# BLDC1.net
KiCad netlist of a schematic drawn in Altium Designer
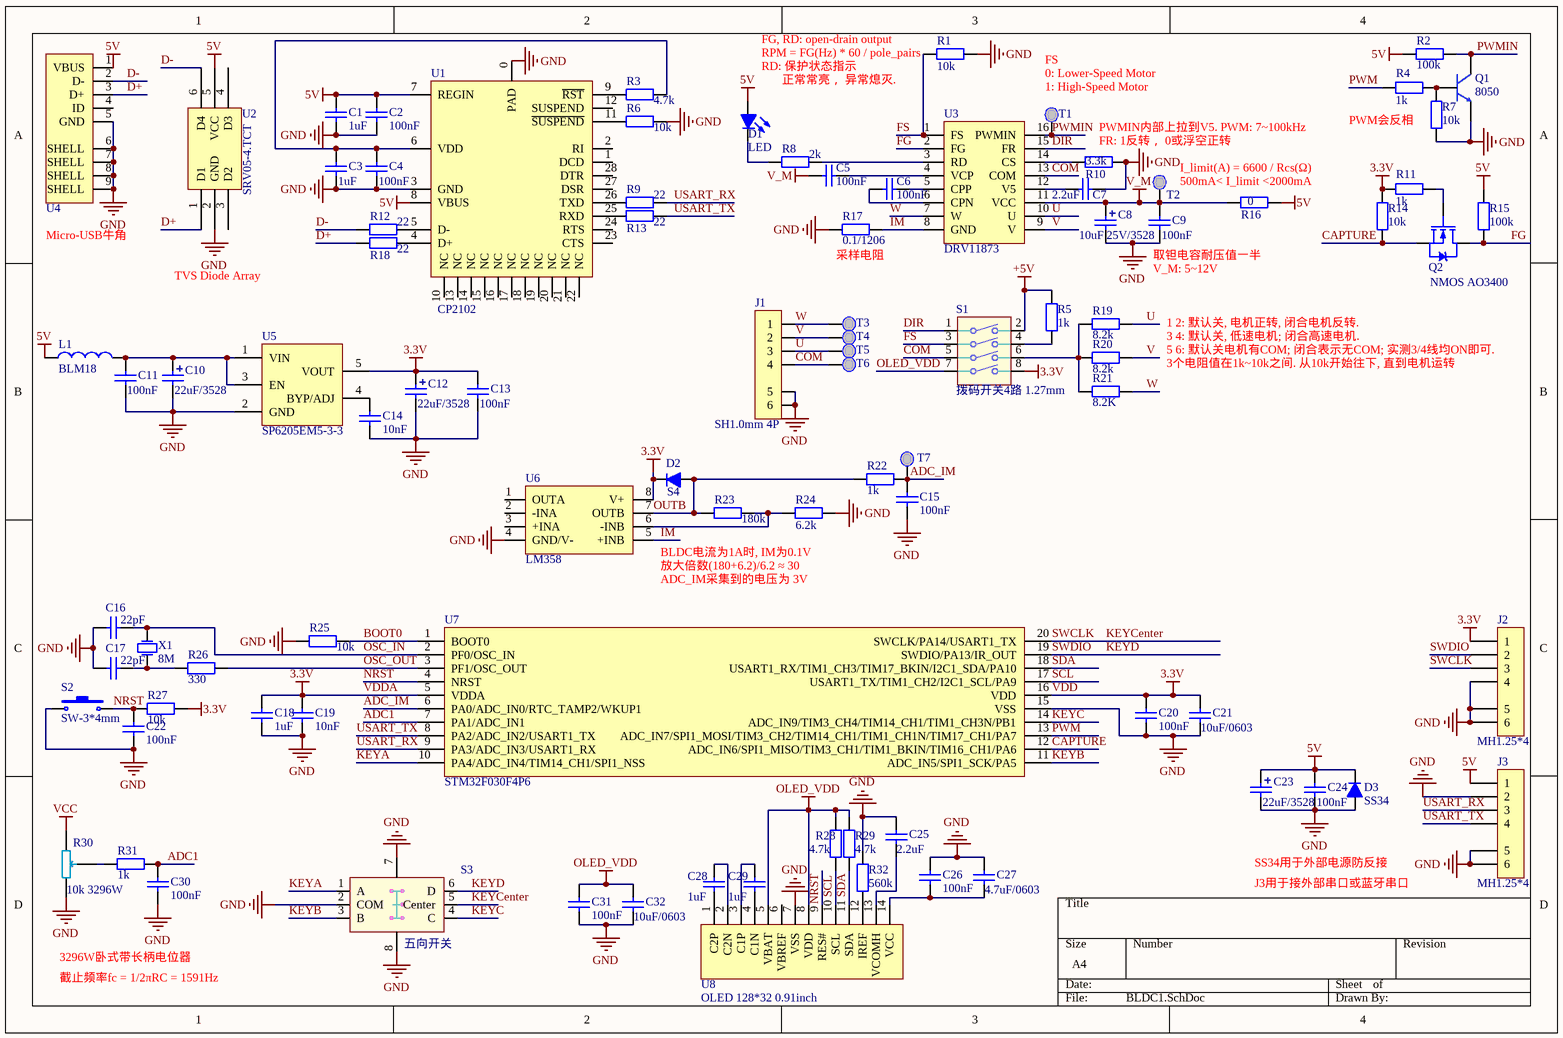
[diagram p0: BLDC1.SchDoc]

(export (version "E")
  (design (tool "Eeschema 10.0.6"))
  (components
    (comp (ref "C1")
      (value "1uF")
      (footprint "C0402")
      (description "Capacitor")
      (fields (field (name "Comment") "Cap1") (field (name "PUBLISHER") "Altium Limited"))
      (libsource (lib "weifengdq") (part "Cap1"))
    )
    (comp (ref "C2")
      (value "100nF")
      (footprint "C0402")
      (description "Capacitor")
      (fields (field (name "Comment") "Cap1") (field (name "PUBLISHER") "Altium Limited"))
      (libsource (lib "weifengdq") (part "Cap1"))
    )
    (comp (ref "C3")
      (value "1uF")
      (footprint "C0402")
      (description "Capacitor")
      (fields (field (name "Comment") "Cap1") (field (name "PUBLISHER") "Altium Limited"))
      (libsource (lib "weifengdq") (part "Cap1"))
    )
    (comp (ref "C4")
      (value "100nF")
      (footprint "C0402")
      (description "Capacitor")
      (fields (field (name "Comment") "Cap1") (field (name "PUBLISHER") "Altium Limited"))
      (libsource (lib "weifengdq") (part "Cap1"))
    )
    (comp (ref "C5")
      (value "100nF")
      (footprint "C0402")
      (description "Capacitor")
      (fields (field (name "Comment") "Cap1") (field (name "PUBLISHER") "Altium Limited"))
      (libsource (lib "weifengdq") (part "Cap1"))
    )
    (comp (ref "C6")
      (value "100nF")
      (footprint "C0402")
      (description "Capacitor")
      (fields (field (name "Comment") "Cap1") (field (name "PUBLISHER") "Altium Limited"))
      (libsource (lib "weifengdq") (part "Cap1"))
    )
    (comp (ref "C7")
      (value "2.2uF")
      (footprint "0603")
      (description "Capacitor")
      (fields (field (name "Comment") "Cap1") (field (name "PUBLISHER") "Altium Limited"))
      (libsource (lib "weifengdq") (part "Cap1"))
    )
    (comp (ref "C8")
      (value "10uF 25V/3528")
      (footprint "3528(22u16V钽电容)")
      (description "Capacitor")
      (fields (field (name "Comment") "Cap_Pol") (field (name "PUBLISHER") "Altium Limited"))
      (libsource (lib "weifengdq") (part "Cap_Pol"))
    )
    (comp (ref "C9")
      (value "100nF")
      (footprint "C0402")
      (description "Capacitor")
      (fields (field (name "Comment") "Cap1") (field (name "PUBLISHER") "Altium Limited"))
      (libsource (lib "weifengdq") (part "Cap1"))
    )
    (comp (ref "C10")
      (value "22uF/3528")
      (footprint "3528(22u16V钽电容)")
      (description "Capacitor")
      (fields (field (name "Comment") "Cap_Pol") (field (name "PUBLISHER") "Altium Limited"))
      (libsource (lib "weifengdq") (part "Cap_Pol"))
    )
    (comp (ref "C11")
      (value "100nF")
      (footprint "C0402")
      (description "Capacitor")
      (fields (field (name "Comment") "Cap1") (field (name "PUBLISHER") "Altium Limited"))
      (libsource (lib "weifengdq") (part "Cap1"))
    )
    (comp (ref "C12")
      (value "22uF/3528")
      (footprint "3528(22u16V钽电容)")
      (description "Capacitor")
      (fields (field (name "Comment") "Cap_Pol") (field (name "PUBLISHER") "Altium Limited"))
      (libsource (lib "weifengdq") (part "Cap_Pol"))
    )
    (comp (ref "C13")
      (value "100nF")
      (footprint "C0402")
      (description "Capacitor")
      (fields (field (name "Comment") "Cap1") (field (name "PUBLISHER") "Altium Limited"))
      (libsource (lib "weifengdq") (part "Cap1"))
    )
    (comp (ref "C14")
      (value "10nF")
      (footprint "C0402")
      (description "Capacitor")
      (fields (field (name "Comment") "Cap1") (field (name "PUBLISHER") "Altium Limited"))
      (libsource (lib "weifengdq") (part "Cap1"))
    )
    (comp (ref "C15")
      (value "100nF")
      (footprint "C0402")
      (description "Capacitor")
      (fields (field (name "Comment") "Cap1") (field (name "PUBLISHER") "Altium Limited"))
      (libsource (lib "weifengdq") (part "Cap1"))
    )
    (comp (ref "C16")
      (value "22pF")
      (footprint "C0402")
      (description "Capacitor")
      (fields (field (name "Comment") "Cap1") (field (name "PUBLISHER") "Altium Limited"))
      (libsource (lib "weifengdq") (part "Cap1"))
    )
    (comp (ref "C17")
      (value "22pF")
      (footprint "C0402")
      (description "Capacitor")
      (fields (field (name "Comment") "Cap1") (field (name "PUBLISHER") "Altium Limited"))
      (libsource (lib "weifengdq") (part "Cap1"))
    )
    (comp (ref "C18")
      (value "1uF")
      (footprint "C0402")
      (description "Capacitor")
      (fields (field (name "Comment") "Cap1") (field (name "PUBLISHER") "Altium Limited"))
      (libsource (lib "weifengdq") (part "Cap1"))
    )
    (comp (ref "C19")
      (value "10nF")
      (footprint "C0402")
      (description "Capacitor")
      (fields (field (name "Comment") "Cap1") (field (name "PUBLISHER") "Altium Limited"))
      (libsource (lib "weifengdq") (part "Cap1"))
    )
    (comp (ref "C20")
      (value "100nF")
      (footprint "C0402")
      (description "Capacitor")
      (fields (field (name "Comment") "Cap1") (field (name "PUBLISHER") "Altium Limited"))
      (libsource (lib "weifengdq") (part "Cap1"))
    )
    (comp (ref "C21")
      (value "10uF/0603")
      (footprint "0603")
      (description "Capacitor")
      (fields (field (name "Comment") "Cap1") (field (name "PUBLISHER") "Altium Limited"))
      (libsource (lib "weifengdq") (part "Cap1"))
    )
    (comp (ref "C22")
      (value "100nF")
      (footprint "C0402")
      (description "Capacitor")
      (fields (field (name "Comment") "Cap1") (field (name "PUBLISHER") "Altium Limited"))
      (libsource (lib "weifengdq") (part "Cap1"))
    )
    (comp (ref "C23")
      (value "22uF/3528")
      (footprint "3528(22u16V钽电容)")
      (description "Capacitor")
      (fields (field (name "Comment") "Cap_Pol") (field (name "PUBLISHER") "Altium Limited"))
      (libsource (lib "weifengdq") (part "Cap_Pol"))
    )
    (comp (ref "C24")
      (value "100nF")
      (footprint "C0402")
      (description "Capacitor")
      (fields (field (name "Comment") "Cap1") (field (name "PUBLISHER") "Altium Limited"))
      (libsource (lib "weifengdq") (part "Cap1"))
    )
    (comp (ref "C25")
      (value "2.2uF")
      (footprint "0603")
      (description "Capacitor")
      (fields (field (name "Comment") "Cap1") (field (name "PUBLISHER") "Altium Limited"))
      (libsource (lib "weifengdq") (part "Cap1"))
    )
    (comp (ref "C26")
      (value "100nF")
      (footprint "C0402")
      (description "Capacitor")
      (fields (field (name "Comment") "Cap1") (field (name "PUBLISHER") "Altium Limited"))
      (libsource (lib "weifengdq") (part "Cap1"))
    )
    (comp (ref "C27")
      (value "4.7uF/0603")
      (footprint "0603")
      (description "Capacitor")
      (fields (field (name "Comment") "Cap1") (field (name "PUBLISHER") "Altium Limited"))
      (libsource (lib "weifengdq") (part "Cap1"))
    )
    (comp (ref "C28")
      (value "1uF")
      (footprint "C0402")
      (description "Capacitor")
      (fields (field (name "Comment") "Cap1") (field (name "PUBLISHER") "Altium Limited"))
      (libsource (lib "weifengdq") (part "Cap1"))
    )
    (comp (ref "C29")
      (value "1uF")
      (footprint "C0402")
      (description "Capacitor")
      (fields (field (name "Comment") "Cap1") (field (name "PUBLISHER") "Altium Limited"))
      (libsource (lib "weifengdq") (part "Cap1"))
    )
    (comp (ref "C30")
      (value "100nF")
      (footprint "C0402")
      (description "Capacitor")
      (fields (field (name "Comment") "Cap1") (field (name "PUBLISHER") "Altium Limited"))
      (libsource (lib "weifengdq") (part "Cap1"))
    )
    (comp (ref "C31")
      (value "100nF")
      (footprint "C0402")
      (description "Capacitor")
      (fields (field (name "Comment") "Cap1") (field (name "PUBLISHER") "Altium Limited"))
      (libsource (lib "weifengdq") (part "Cap1"))
    )
    (comp (ref "C32")
      (value "10uF/0603")
      (footprint "0603")
      (description "Capacitor")
      (fields (field (name "Comment") "Cap1") (field (name "PUBLISHER") "Altium Limited"))
      (libsource (lib "weifengdq") (part "Cap1"))
    )
    (comp (ref "D1")
      (value "LED")
      (footprint "DIODE-12")
      (description "Typical INFRARED GaAs LED")
      (fields (field (name "PUBLISHER") "Altium Limited"))
      (libsource (lib "weifengdq") (part "LED1"))
    )
    (comp (ref "D2") (value "S4") (footprint "Diode-0805") (libsource (lib "weifengdq") (part "Diode1")))
    (comp (ref "D3")
      (value "SS34")
      (footprint "LC-SMA(DO-214AC)_S2")
      (libsource (lib "weifengdq") (part "Diode1"))
    )
    (comp (ref "J1")
      (value "SH1.0mm 4P")
      (footprint "SH1.0 4P")
      (libsource (lib "weifengdq") (part "SH1.0mm 4P"))
    )
    (comp (ref "J2")
      (value "MH1.25*4")
      (footprint "MH1.25*4立式表贴")
      (libsource (lib "weifengdq") (part "MH1.25*4卧式贴片"))
    )
    (comp (ref "J3")
      (value "MH1.25*4")
      (footprint "MH1.25*4立式表贴")
      (libsource (lib "weifengdq") (part "MH1.25*4卧式贴片"))
    )
    (comp (ref "L1") (value "BLM18") (footprint "CC0805") (libsource (lib "weifengdq") (part "BLM18")))
    (comp (ref "Q1") (value "8050") (footprint "SOT-23-3") (libsource (lib "weifengdq") (part "NPN")))
    (comp (ref "Q2")
      (value "NMOS AO3400")
      (footprint "SOT-23-3 - AO3400")
      (description "N-Channel Power MOSFET")
      (fields (field (name "PUBLISHER") "Altium Limited"))
      (libsource (lib "weifengdq") (part "NMOS"))
    )
    (comp (ref "R1")
      (value "10k")
      (footprint "C0402")
      (description "Resistor")
      (fields (field (name "Comment") "Res1") (field (name "PUBLISHER") "Altium Limited"))
      (libsource (lib "") (part "Res1_1"))
    )
    (comp (ref "R2")
      (value "100k")
      (footprint "C0402")
      (description "Resistor")
      (fields (field (name "Comment") "Res1") (field (name "PUBLISHER") "Altium Limited"))
      (libsource (lib "") (part "Res1_1"))
    )
    (comp (ref "R3")
      (value "4.7k")
      (footprint "C0402")
      (description "Resistor")
      (fields (field (name "Comment") "Res1") (field (name "PUBLISHER") "Altium Limited"))
      (libsource (lib "weifengdq") (part "Res1"))
    )
    (comp (ref "R4")
      (value "1k")
      (footprint "C0402")
      (description "Resistor")
      (fields (field (name "Comment") "Res1") (field (name "PUBLISHER") "Altium Limited"))
      (libsource (lib "weifengdq") (part "Res1"))
    )
    (comp (ref "R5")
      (value "1k")
      (footprint "C0402")
      (description "Resistor")
      (fields (field (name "Comment") "Res1") (field (name "PUBLISHER") "Altium Limited"))
      (libsource (lib "") (part "Res1_3"))
    )
    (comp (ref "R6")
      (value "10k")
      (footprint "C0402")
      (description "Resistor")
      (fields (field (name "Comment") "Res1") (field (name "PUBLISHER") "Altium Limited"))
      (libsource (lib "weifengdq") (part "Res1"))
    )
    (comp (ref "R7")
      (value "10k")
      (footprint "C0402")
      (description "Resistor")
      (fields (field (name "Comment") "Res1") (field (name "PUBLISHER") "Altium Limited"))
      (libsource (lib "") (part "Res1_2"))
    )
    (comp (ref "R8")
      (value "2k")
      (footprint "C0402")
      (description "Resistor")
      (fields (field (name "Comment") "Res1") (field (name "PUBLISHER") "Altium Limited"))
      (libsource (lib "") (part "Res1_1"))
    )
    (comp (ref "R9")
      (value "22")
      (footprint "C0402")
      (description "Resistor")
      (fields (field (name "Comment") "Res1") (field (name "PUBLISHER") "Altium Limited"))
      (libsource (lib "weifengdq") (part "Res1"))
    )
    (comp (ref "R10")
      (value "3.3k")
      (footprint "C0402")
      (description "Resistor")
      (fields (field (name "Comment") "Res1") (field (name "PUBLISHER") "Altium Limited"))
      (libsource (lib "weifengdq") (part "Res1"))
    )
    (comp (ref "R11")
      (value "1k")
      (footprint "C0402")
      (description "Resistor")
      (fields (field (name "Comment") "Res1") (field (name "PUBLISHER") "Altium Limited"))
      (libsource (lib "weifengdq") (part "Res1"))
    )
    (comp (ref "R12")
      (value "22")
      (footprint "C0402")
      (description "Resistor")
      (fields (field (name "Comment") "Res1") (field (name "PUBLISHER") "Altium Limited"))
      (libsource (lib "weifengdq") (part "Res1"))
    )
    (comp (ref "R13")
      (value "22")
      (footprint "C0402")
      (description "Resistor")
      (fields (field (name "Comment") "Res1") (field (name "PUBLISHER") "Altium Limited"))
      (libsource (lib "weifengdq") (part "Res1"))
    )
    (comp (ref "R14")
      (value "10k")
      (footprint "C0402")
      (description "Resistor")
      (fields (field (name "Comment") "Res1") (field (name "PUBLISHER") "Altium Limited"))
      (libsource (lib "") (part "Res1_2"))
    )
    (comp (ref "R15")
      (value "100k")
      (footprint "C0402")
      (description "Resistor")
      (fields (field (name "Comment") "Res1") (field (name "PUBLISHER") "Altium Limited"))
      (libsource (lib "") (part "Res1_2"))
    )
    (comp (ref "R16")
      (value "0")
      (footprint "C0805")
      (description "Resistor")
      (fields (field (name "Comment") "Res1") (field (name "PUBLISHER") "Altium Limited"))
      (libsource (lib "weifengdq") (part "Res1"))
    )
    (comp (ref "R17")
      (value "0.1/1206")
      (footprint "3216[1206]")
      (description "Resistor")
      (fields (field (name "Comment") "Res1") (field (name "PUBLISHER") "Altium Limited"))
      (libsource (lib "") (part "Res1_1"))
    )
    (comp (ref "R18")
      (value "22")
      (footprint "C0402")
      (description "Resistor")
      (fields (field (name "Comment") "Res1") (field (name "PUBLISHER") "Altium Limited"))
      (libsource (lib "weifengdq") (part "Res1"))
    )
    (comp (ref "R19")
      (value "8.2k")
      (footprint "C0402")
      (description "Resistor")
      (fields (field (name "Comment") "Res1") (field (name "PUBLISHER") "Altium Limited"))
      (libsource (lib "") (part "Res1_1"))
    )
    (comp (ref "R20")
      (value "8.2k")
      (footprint "C0402")
      (description "Resistor")
      (fields (field (name "Comment") "Res1") (field (name "PUBLISHER") "Altium Limited"))
      (libsource (lib "") (part "Res1_1"))
    )
    (comp (ref "R21")
      (value "8.2K")
      (footprint "C0402")
      (description "Resistor")
      (fields (field (name "Comment") "Res1") (field (name "PUBLISHER") "Altium Limited"))
      (libsource (lib "") (part "Res1_1"))
    )
    (comp (ref "R22")
      (value "1k")
      (footprint "C0402")
      (description "Resistor")
      (fields (field (name "Comment") "Res1") (field (name "PUBLISHER") "Altium Limited"))
      (libsource (lib "") (part "Res1_1"))
    )
    (comp (ref "R23")
      (value "180k")
      (footprint "C0402")
      (description "Resistor")
      (fields (field (name "Comment") "Res1") (field (name "PUBLISHER") "Altium Limited"))
      (libsource (lib "weifengdq") (part "Res1"))
    )
    (comp (ref "R24")
      (value "6.2k")
      (footprint "C0402")
      (description "Resistor")
      (fields (field (name "Comment") "Res1") (field (name "PUBLISHER") "Altium Limited"))
      (libsource (lib "weifengdq") (part "Res1"))
    )
    (comp (ref "R25")
      (value "10k")
      (footprint "C0402")
      (description "Resistor")
      (fields (field (name "Comment") "Res1") (field (name "PUBLISHER") "Altium Limited"))
      (libsource (lib "") (part "Res1_1"))
    )
    (comp (ref "R26")
      (value "330")
      (footprint "C0402")
      (description "Resistor")
      (fields (field (name "Comment") "Res1") (field (name "PUBLISHER") "Altium Limited"))
      (libsource (lib "") (part "Res1_1"))
    )
    (comp (ref "R27")
      (value "10k")
      (footprint "C0402")
      (description "Resistor")
      (fields (field (name "Comment") "Res1") (field (name "PUBLISHER") "Altium Limited"))
      (libsource (lib "") (part "Res1_1"))
    )
    (comp (ref "R28")
      (value "4.7k")
      (footprint "C0402")
      (description "Resistor")
      (fields (field (name "Comment") "Res1") (field (name "PUBLISHER") "Altium Limited"))
      (libsource (lib "") (part "Res1_2"))
    )
    (comp (ref "R29")
      (value "4.7k")
      (footprint "C0402")
      (description "Resistor")
      (fields (field (name "Comment") "Res1") (field (name "PUBLISHER") "Altium Limited"))
      (libsource (lib "") (part "Res1_2"))
    )
    (comp (ref "R30")
      (value "10k 3296W")
      (footprint "3296W 卧式")
      (libsource (lib "weifengdq") (part "Res_3296"))
    )
    (comp (ref "R31")
      (value "1k")
      (footprint "C0402")
      (description "Resistor")
      (fields (field (name "Comment") "Res1") (field (name "PUBLISHER") "Altium Limited"))
      (libsource (lib "") (part "Res1_1"))
    )
    (comp (ref "R32")
      (value "560k")
      (footprint "C0402")
      (description "Resistor")
      (fields (field (name "Comment") "Res1") (field (name "PUBLISHER") "Altium Limited"))
      (libsource (lib "") (part "Res1_2"))
    )
    (comp (ref "S1")
      (value "拨码开关4路 1.27mm")
      (footprint "拨码开关4路")
      (libsource (lib "weifengdq") (part "拨码开关4路 1.27mm"))
    )
    (comp (ref "S2")
      (value "SW-3*4mm")
      (footprint "SW-3*4mm")
      (description "Switch")
      (fields (field (name "PUBLISHER") "Altium Limited"))
      (libsource (lib "weifengdq") (part "SW-3*4mm"))
    )
    (comp (ref "S3")
      (value "五向开关")
      (footprint "五向开关")
      (description "Switch")
      (fields (field (name "PUBLISHER") "Altium Limited"))
      (libsource (lib "weifengdq") (part "五向开关"))
    )
    (comp (ref "T1") (value "TEST") (footprint "TEST") (libsource (lib "weifengdq") (part "TEST")))
    (comp (ref "T2") (value "TEST") (footprint "TEST") (libsource (lib "weifengdq") (part "TEST")))
    (comp (ref "T3") (value "TEST") (footprint "TEST") (libsource (lib "weifengdq") (part "TEST")))
    (comp (ref "T4") (value "TEST") (footprint "TEST") (libsource (lib "weifengdq") (part "TEST")))
    (comp (ref "T5") (value "TEST") (footprint "TEST") (libsource (lib "weifengdq") (part "TEST")))
    (comp (ref "T6") (value "TEST") (footprint "TEST") (libsource (lib "weifengdq") (part "TEST")))
    (comp (ref "T7") (value "TEST") (footprint "TEST") (libsource (lib "weifengdq") (part "TEST")))
    (comp (ref "U1")
      (value "CP2102")
      (footprint "LC-QFN-28_5x5x05P")
      (libsource (lib "weifengdq") (part "CP2102"))
    )
    (comp (ref "U2")
      (value "SRV05-4.TCT")
      (footprint "LC-SOT-23-6")
      (libsource (lib "weifengdq") (part "SRV05-4.TCT"))
    )
    (comp (ref "U3")
      (value "DRV11873")
      (footprint "HTSSOP16")
      (libsource (lib "weifengdq") (part "DRV11873"))
    )
    (comp (ref "U4")
      (value "Micro-USB-N")
      (footprint "Micro-USB-N")
      (libsource (lib "weifengdq") (part "Micro-USB-N"))
    )
    (comp (ref "U5")
      (value "SP6205EM5-3-3")
      (footprint "LC-SOT-23-5")
      (libsource (lib "weifengdq") (part "SP6205EM5-L-3-3"))
    )
    (comp (ref "U6") (value "LM358") (footprint "LC-SOIC-8") (libsource (lib "weifengdq") (part "LM358")))
    (comp (ref "U7")
      (value "STM32F030F4P6")
      (footprint "TSSOP20")
      (libsource (lib "weifengdq") (part "STM32F030F4P6"))
    )
    (comp (ref "U8")
      (value "OLED 128*32 0.91inch")
      (footprint "OLED 0.91 I2C")
      (libsource (lib "weifengdq") (part "OLED 12832 I2C"))
    )
    (comp (ref "X1")
      (value "8M")
      (footprint "XTAL-3225")
      (description "Crystal Oscillator")
      (fields (field (name "PUBLISHER") "Altium Limited"))
      (libsource (lib "weifengdq") (part "XTAL_1"))
    )
  )
  (nets
    (net (code "1") (name "+5V") (class "Default")
      (node (ref "R5") (pin "1") (pinfunction "1_1") (pintype "passive"))
      (node (ref "S1") (pin "2") (pinfunction "2_2") (pintype "passive"))
    )
    (net (code "2") (name "/ADC1") (class "Default")
      (node (ref "C30") (pin "2") (pinfunction "2_2") (pintype "passive"))
      (node (ref "R31") (pin "1") (pinfunction "1_1") (pintype "passive"))
      (node (ref "U7") (pin "7") (pinfunction "PA1/ADC_IN1_7") (pintype "passive"))
    )
    (net (code "3") (name "/ADC_IM") (class "Default")
      (node (ref "C15") (pin "2") (pinfunction "2_2") (pintype "passive"))
      (node (ref "R22") (pin "1") (pinfunction "1_1") (pintype "passive"))
      (node (ref "T7") (pin "1") (pinfunction "1_1") (pintype "passive"))
      (node (ref "U7") (pin "6") (pinfunction "PA0/ADC_IN0/RTC_TAMP2/WKUP1_6") (pintype "passive"))
    )
    (net (code "4") (name "/BOOT0") (class "Default")
      (node (ref "R25") (pin "1") (pinfunction "1_1") (pintype "passive"))
      (node (ref "U7") (pin "1") (pinfunction "BOOT0_1") (pintype "passive"))
    )
    (net (code "5") (name "/CAPTURE") (class "Default")
      (node (ref "Q2") (pin "3") (pinfunction "S_3") (pintype "passive"))
      (node (ref "R14") (pin "1") (pinfunction "1_1") (pintype "passive"))
      (node (ref "U7") (pin "12") (pinfunction "ADC_IN6/SPI1_MISO/TIM3_CH1/TIM1_BKIN/TIM16_CH1/PA6_12") (pintype "passive"))
    )
    (net (code "6") (name "/COM") (class "Default")
      (node (ref "J1") (pin "4") (pinfunction "4_4") (pintype "passive"))
      (node (ref "S1") (pin "5") (pinfunction "5_5") (pintype "passive"))
      (node (ref "T6") (pin "1") (pinfunction "1_1") (pintype "passive"))
      (node (ref "U3") (pin "13") (pinfunction "COM_13") (pintype "passive"))
    )
    (net (code "7") (name "/D+") (class "Default")
      (node (ref "R18") (pin "1") (pinfunction "1_1") (pintype "passive"))
      (node (ref "U2") (pin "1") (pinfunction "D1_1") (pintype "passive"))
      (node (ref "U4") (pin "3") (pinfunction "D+_3") (pintype "passive"))
    )
    (net (code "8") (name "/D-") (class "Default")
      (node (ref "R12") (pin "1") (pinfunction "1_1") (pintype "passive"))
      (node (ref "U2") (pin "6") (pinfunction "D4_6") (pintype "passive"))
      (node (ref "U4") (pin "2") (pinfunction "D-_2") (pintype "passive"))
    )
    (net (code "9") (name "/DIR") (class "Default")
      (node (ref "S1") (pin "1") (pinfunction "1_1") (pintype "passive"))
      (node (ref "U3") (pin "15") (pinfunction "FR_15") (pintype "passive"))
    )
    (net (code "10") (name "/FG") (class "Default")
      (node (ref "Q2") (pin "2") (pinfunction "D_2") (pintype "passive"))
      (node (ref "R15") (pin "1") (pinfunction "1_1") (pintype "passive"))
      (node (ref "U3") (pin "2") (pinfunction "FG_2") (pintype "passive"))
    )
    (net (code "11") (name "/FS") (class "Default")
      (node (ref "R1") (pin "2") (pinfunction "2_2") (pintype "passive"))
      (node (ref "S1") (pin "3") (pinfunction "3_3") (pintype "passive"))
      (node (ref "U3") (pin "1") (pinfunction "FS_1") (pintype "passive"))
    )
    (net (code "12") (name "/IM") (class "Default")
      (node (ref "R17") (pin "1") (pinfunction "1_1") (pintype "passive"))
      (node (ref "U3") (pin "8") (pinfunction "GND_8") (pintype "passive"))
      (node (ref "U6") (pin "5") (pinfunction "+INB_5") (pintype "passive"))
    )
    (net (code "13") (name "/KEYA") (class "Default")
      (node (ref "S3") (pin "1") (pinfunction "A_1") (pintype "passive"))
      (node (ref "U7") (pin "10") (pinfunction "PA4/ADC_IN4/TIM14_CH1/SPI1_NSS_10") (pintype "passive"))
    )
    (net (code "14") (name "/KEYB") (class "Default")
      (node (ref "S3") (pin "3") (pinfunction "B_3") (pintype "passive"))
      (node (ref "U7") (pin "11") (pinfunction "ADC_IN5/SPI1_SCK/PA5_11") (pintype "passive"))
    )
    (net (code "15") (name "/KEYC") (class "Default")
      (node (ref "S3") (pin "4") (pinfunction "C_4") (pintype "passive"))
      (node (ref "U7") (pin "14") (pinfunction "ADC_IN9/TIM3_CH4/TIM14_CH1/TIM1_CH3N/PB1_14") (pintype "passive"))
    )
    (net (code "16") (name "/KEYCenter") (class "Default")
      (node (ref "J2") (pin "3") (pinfunction "3_3") (pintype "passive"))
      (node (ref "S3") (pin "5") (pinfunction "Center_5") (pintype "passive"))
      (node (ref "U7") (pin "20") (pinfunction "SWCLK/PA14/USART1_TX_20") (pintype "passive"))
    )
    (net (code "17") (name "/KEYD") (class "Default")
      (node (ref "J2") (pin "2") (pinfunction "2_2") (pintype "passive"))
      (node (ref "S3") (pin "6") (pinfunction "D_6") (pintype "passive"))
      (node (ref "U7") (pin "19") (pinfunction "SWDIO/PA13/IR_OUT_19") (pintype "passive"))
    )
    (net (code "18") (name "/NRST") (class "Default")
      (node (ref "C22") (pin "2") (pinfunction "2_2") (pintype "passive"))
      (node (ref "R27") (pin "2") (pinfunction "2_2") (pintype "passive"))
      (node (ref "S2") (pin "2") (pinfunction "2_2") (pintype "passive"))
      (node (ref "U7") (pin "4") (pinfunction "NRST_4") (pintype "passive"))
      (node (ref "U8") (pin "9") (pinfunction "RES#_9") (pintype "passive"))
    )
    (net (code "19") (name "/OSC_IN") (class "Default")
      (node (ref "C16") (pin "2") (pinfunction "2_2") (pintype "passive"))
      (node (ref "U7") (pin "2") (pinfunction "PF0/OSC_IN_2") (pintype "passive"))
      (node (ref "X1") (pin "2") (pinfunction "OSC2_2") (pintype "passive"))
    )
    (net (code "20") (name "/OSC_OUT") (class "Default")
      (node (ref "R26") (pin "1") (pinfunction "1_1") (pintype "passive"))
      (node (ref "U7") (pin "3") (pinfunction "PF1/OSC_OUT_3") (pintype "passive"))
    )
    (net (code "21") (name "/OUTB") (class "Default")
      (node (ref "D2") (pin "1") (pinfunction "A_1") (pintype "passive"))
      (node (ref "R22") (pin "2") (pinfunction "2_2") (pintype "passive"))
      (node (ref "R23") (pin "1") (pinfunction "1_1") (pintype "passive"))
      (node (ref "U6") (pin "7") (pinfunction "OUTB_7") (pintype "passive"))
    )
    (net (code "22") (name "/PWM") (class "Default")
      (node (ref "R4") (pin "1") (pinfunction "1_1") (pintype "passive"))
      (node (ref "U7") (pin "13") (pinfunction "ADC_IN7/SPI1_MOSI/TIM3_CH2/TIM14_CH1/TIM1_CH1N/TIM17_CH1/PA7_13") (pintype "passive"))
    )
    (net (code "23") (name "/PWMIN") (class "Default")
      (node (ref "Q1") (pin "3") (pinfunction "c_3") (pintype "passive"))
      (node (ref "R2") (pin "1") (pinfunction "1_1") (pintype "passive"))
      (node (ref "T1") (pin "1") (pinfunction "1_1") (pintype "passive"))
      (node (ref "U3") (pin "16") (pinfunction "PWMIN_16") (pintype "passive"))
    )
    (net (code "24") (name "/SCL") (class "Default")
      (node (ref "R28") (pin "1") (pinfunction "1_1") (pintype "passive"))
      (node (ref "U7") (pin "17") (pinfunction "USART1_TX/TIM1_CH2/I2C1_SCL/PA9_17") (pintype "passive"))
      (node (ref "U8") (pin "10") (pinfunction "SCL_10") (pintype "passive"))
    )
    (net (code "25") (name "/SDA") (class "Default")
      (node (ref "R29") (pin "1") (pinfunction "1_1") (pintype "passive"))
      (node (ref "U7") (pin "18") (pinfunction "USART1_RX/TIM1_CH3/TIM17_BKIN/I2C1_SDA/PA10_18") (pintype "passive"))
      (node (ref "U8") (pin "11") (pinfunction "SDA_11") (pintype "passive"))
    )
    (net (code "26") (name "/U") (class "Default")
      (node (ref "J1") (pin "3") (pinfunction "3_3") (pintype "passive"))
      (node (ref "R19") (pin "1") (pinfunction "1_1") (pintype "passive"))
      (node (ref "T5") (pin "1") (pinfunction "1_1") (pintype "passive"))
      (node (ref "U3") (pin "10") (pinfunction "U_10") (pintype "passive"))
    )
    (net (code "27") (name "/USART_RX") (class "Default")
      (node (ref "J3") (pin "3") (pinfunction "3_3") (pintype "passive"))
      (node (ref "R9") (pin "2") (pinfunction "2_2") (pintype "passive"))
      (node (ref "U7") (pin "9") (pinfunction "PA3/ADC_IN3/USART1_RX_9") (pintype "passive"))
    )
    (net (code "28") (name "/USART_TX") (class "Default")
      (node (ref "J3") (pin "4") (pinfunction "4_4") (pintype "passive"))
      (node (ref "R13") (pin "2") (pinfunction "2_2") (pintype "passive"))
      (node (ref "U7") (pin "8") (pinfunction "PA2/ADC_IN2/USART1_TX_8") (pintype "passive"))
    )
    (net (code "29") (name "/V") (class "Default")
      (node (ref "J1") (pin "2") (pinfunction "2_2") (pintype "passive"))
      (node (ref "R20") (pin "1") (pinfunction "1_1") (pintype "passive"))
      (node (ref "T4") (pin "1") (pinfunction "1_1") (pintype "passive"))
      (node (ref "U3") (pin "9") (pinfunction "V_9") (pintype "passive"))
    )
    (net (code "30") (name "/W") (class "Default")
      (node (ref "J1") (pin "1") (pinfunction "1_1") (pintype "passive"))
      (node (ref "R21") (pin "1") (pinfunction "1_1") (pintype "passive"))
      (node (ref "T3") (pin "1") (pinfunction "1_1") (pintype "passive"))
      (node (ref "U3") (pin "7") (pinfunction "W_7") (pintype "passive"))
    )
    (net (code "31") (name "3.3V") (class "Default")
      (node (ref "C12") (pin "1") (pinfunction "1_1") (pintype "passive"))
      (node (ref "C13") (pin "2") (pinfunction "2_2") (pintype "passive"))
      (node (ref "C18") (pin "2") (pinfunction "2_2") (pintype "passive"))
      (node (ref "C19") (pin "2") (pinfunction "2_2") (pintype "passive"))
      (node (ref "C20") (pin "2") (pinfunction "2_2") (pintype "passive"))
      (node (ref "C21") (pin "2") (pinfunction "2_2") (pintype "passive"))
      (node (ref "D2") (pin "2") (pinfunction "K_2") (pintype "passive"))
      (node (ref "J2") (pin "1") (pinfunction "1_1") (pintype "passive"))
      (node (ref "R11") (pin "1") (pinfunction "1_1") (pintype "passive"))
      (node (ref "R14") (pin "2") (pinfunction "2_2") (pintype "passive"))
      (node (ref "R27") (pin "1") (pinfunction "1_1") (pintype "passive"))
      (node (ref "S1") (pin "8") (pinfunction "8_8") (pintype "passive"))
      (node (ref "U5") (pin "5") (pinfunction "VOUT_5") (pintype "passive"))
      (node (ref "U6") (pin "8") (pinfunction "V+_8") (pintype "passive"))
      (node (ref "U7") (pin "16") (pinfunction "VDD_16") (pintype "passive"))
      (node (ref "U7") (pin "5") (pinfunction "VDDA_5") (pintype "passive"))
    )
    (net (code "32") (name "5V") (class "Default")
      (node (ref "C1") (pin "2") (pinfunction "2_2") (pintype "passive"))
      (node (ref "C2") (pin "2") (pinfunction "2_2") (pintype "passive"))
      (node (ref "C23") (pin "1") (pinfunction "1_1") (pintype "passive"))
      (node (ref "C24") (pin "2") (pinfunction "2_2") (pintype "passive"))
      (node (ref "D1") (pin "1") (pinfunction "A_1") (pintype "passive"))
      (node (ref "D3") (pin "2") (pinfunction "K_2") (pintype "passive"))
      (node (ref "J3") (pin "1") (pinfunction "1_1") (pintype "passive"))
      (node (ref "L1") (pin "1") (pinfunction "1_1") (pintype "passive"))
      (node (ref "R15") (pin "2") (pinfunction "2_2") (pintype "passive"))
      (node (ref "R16") (pin "2") (pinfunction "2_2") (pintype "passive"))
      (node (ref "R2") (pin "2") (pinfunction "2_2") (pintype "passive"))
      (node (ref "U1") (pin "7") (pinfunction "REGIN_7") (pintype "passive"))
      (node (ref "U1") (pin "8") (pinfunction "VBUS_8") (pintype "passive"))
      (node (ref "U2") (pin "5") (pinfunction "VCC_5") (pintype "passive"))
      (node (ref "U4") (pin "1") (pinfunction "VBUS_1") (pintype "passive"))
    )
    (net (code "33") (name "GND") (class "Default")
      (node (ref "C1") (pin "1") (pinfunction "1_1") (pintype "passive"))
      (node (ref "C10") (pin "2") (pinfunction "2_2") (pintype "passive"))
      (node (ref "C11") (pin "1") (pinfunction "1_1") (pintype "passive"))
      (node (ref "C12") (pin "2") (pinfunction "2_2") (pintype "passive"))
      (node (ref "C13") (pin "1") (pinfunction "1_1") (pintype "passive"))
      (node (ref "C14") (pin "1") (pinfunction "1_1") (pintype "passive"))
      (node (ref "C15") (pin "1") (pinfunction "1_1") (pintype "passive"))
      (node (ref "C16") (pin "1") (pinfunction "1_1") (pintype "passive"))
      (node (ref "C17") (pin "1") (pinfunction "1_1") (pintype "passive"))
      (node (ref "C18") (pin "1") (pinfunction "1_1") (pintype "passive"))
      (node (ref "C19") (pin "1") (pinfunction "1_1") (pintype "passive"))
      (node (ref "C2") (pin "1") (pinfunction "1_1") (pintype "passive"))
      (node (ref "C20") (pin "1") (pinfunction "1_1") (pintype "passive"))
      (node (ref "C21") (pin "1") (pinfunction "1_1") (pintype "passive"))
      (node (ref "C22") (pin "1") (pinfunction "1_1") (pintype "passive"))
      (node (ref "C23") (pin "2") (pinfunction "2_2") (pintype "passive"))
      (node (ref "C24") (pin "1") (pinfunction "1_1") (pintype "passive"))
      (node (ref "C25") (pin "1") (pinfunction "1_1") (pintype "passive"))
      (node (ref "C26") (pin "2") (pinfunction "2_2") (pintype "passive"))
      (node (ref "C27") (pin "2") (pinfunction "2_2") (pintype "passive"))
      (node (ref "C3") (pin "1") (pinfunction "1_1") (pintype "passive"))
      (node (ref "C30") (pin "1") (pinfunction "1_1") (pintype "passive"))
      (node (ref "C31") (pin "1") (pinfunction "1_1") (pintype "passive"))
      (node (ref "C32") (pin "1") (pinfunction "1_1") (pintype "passive"))
      (node (ref "C4") (pin "1") (pinfunction "1_1") (pintype "passive"))
      (node (ref "C7") (pin "1") (pinfunction "1_1") (pintype "passive"))
      (node (ref "C8") (pin "2") (pinfunction "2_2") (pintype "passive"))
      (node (ref "C9") (pin "1") (pinfunction "1_1") (pintype "passive"))
      (node (ref "D3") (pin "1") (pinfunction "A_1") (pintype "passive"))
      (node (ref "J1") (pin "5") (pinfunction "5_5") (pintype "passive"))
      (node (ref "J1") (pin "6") (pinfunction "6_6") (pintype "passive"))
      (node (ref "J2") (pin "4") (pinfunction "4_4") (pintype "passive"))
      (node (ref "J2") (pin "5") (pinfunction "5_5") (pintype "passive"))
      (node (ref "J2") (pin "6") (pinfunction "6_6") (pintype "passive"))
      (node (ref "J3") (pin "2") (pinfunction "2_2") (pintype "passive"))
      (node (ref "J3") (pin "5") (pinfunction "5_5") (pintype "passive"))
      (node (ref "J3") (pin "6") (pinfunction "6_6") (pintype "passive"))
      (node (ref "Q1") (pin "1") (pinfunction "e_1") (pintype "passive"))
      (node (ref "R1") (pin "1") (pinfunction "1_1") (pintype "passive"))
      (node (ref "R10") (pin "2") (pinfunction "2_2") (pintype "passive"))
      (node (ref "R17") (pin "2") (pinfunction "2_2") (pintype "passive"))
      (node (ref "R24") (pin "2") (pinfunction "2_2") (pintype "passive"))
      (node (ref "R25") (pin "2") (pinfunction "2_2") (pintype "passive"))
      (node (ref "R30") (pin "3") (pinfunction "3_3") (pintype "passive"))
      (node (ref "R32") (pin "2") (pinfunction "2_2") (pintype "passive"))
      (node (ref "R6") (pin "2") (pinfunction "2_2") (pintype "passive"))
      (node (ref "R7") (pin "1") (pinfunction "1_1") (pintype "passive"))
      (node (ref "S2") (pin "1") (pinfunction "1_1") (pintype "passive"))
      (node (ref "S3") (pin "2") (pinfunction "COM_2") (pintype "passive"))
      (node (ref "S3") (pin "7") (pinfunction "7_7") (pintype "passive"))
      (node (ref "S3") (pin "8") (pinfunction "8_8") (pintype "passive"))
      (node (ref "U1") (pin "0") (pinfunction "PAD_0") (pintype "passive"))
      (node (ref "U1") (pin "3") (pinfunction "GND_3") (pintype "passive"))
      (node (ref "U2") (pin "2") (pinfunction "GND_2") (pintype "passive"))
      (node (ref "U4") (pin "5") (pinfunction "GND_5") (pintype "passive"))
      (node (ref "U4") (pin "6") (pinfunction "SHELL_6") (pintype "passive"))
      (node (ref "U4") (pin "7") (pinfunction "SHELL_7") (pintype "passive"))
      (node (ref "U4") (pin "8") (pinfunction "SHELL_8") (pintype "passive"))
      (node (ref "U4") (pin "9") (pinfunction "SHELL_9") (pintype "passive"))
      (node (ref "U5") (pin "2") (pinfunction "GND_2") (pintype "passive"))
      (node (ref "U6") (pin "4") (pinfunction "GND/V-_4") (pintype "passive"))
      (node (ref "U7") (pin "15") (pinfunction "VSS_15") (pintype "passive"))
      (node (ref "U8") (pin "7") (pinfunction "VSS_7") (pintype "passive"))
    )
    (net (code "34") (name "Net-(D1-K)") (class "Default")
      (node (ref "D1") (pin "2") (pinfunction "K_2") (pintype "passive"))
      (node (ref "R8") (pin "2") (pinfunction "2_2") (pintype "passive"))
    )
    (net (code "35") (name "Net-(Q1-b)") (class "Default")
      (node (ref "Q1") (pin "2") (pinfunction "b_2") (pintype "passive"))
      (node (ref "R4") (pin "2") (pinfunction "2_2") (pintype "passive"))
      (node (ref "R7") (pin "2") (pinfunction "2_2") (pintype "passive"))
    )
    (net (code "36") (name "Net-(Q2-G)") (class "Default")
      (node (ref "Q2") (pin "1") (pinfunction "G_1") (pintype "passive"))
      (node (ref "R11") (pin "2") (pinfunction "2_2") (pintype "passive"))
    )
    (net (code "37") (name "Net-(R5-Pad2)") (class "Default")
      (node (ref "R5") (pin "2") (pinfunction "2_2") (pintype "passive"))
      (node (ref "S1") (pin "4") (pinfunction "4_4") (pintype "passive"))
    )
    (net (code "38") (name "Net-(R19-Pad2)") (class "Default")
      (node (ref "R19") (pin "2") (pinfunction "2_2") (pintype "passive"))
      (node (ref "R20") (pin "2") (pinfunction "2_2") (pintype "passive"))
      (node (ref "R21") (pin "2") (pinfunction "2_2") (pintype "passive"))
      (node (ref "S1") (pin "6") (pinfunction "6_6") (pintype "passive"))
    )
    (net (code "39") (name "Net-(R30-Pad2)") (class "Default")
      (node (ref "R30") (pin "2") (pinfunction "2_2") (pintype "passive"))
      (node (ref "R31") (pin "2") (pinfunction "2_2") (pintype "passive"))
    )
    (net (code "40") (name "Net-(U1-D+)") (class "Default")
      (node (ref "R18") (pin "2") (pinfunction "2_2") (pintype "passive"))
      (node (ref "U1") (pin "4") (pinfunction "D+_4") (pintype "passive"))
    )
    (net (code "41") (name "Net-(U1-D-)") (class "Default")
      (node (ref "R12") (pin "2") (pinfunction "2_2") (pintype "passive"))
      (node (ref "U1") (pin "5") (pinfunction "D-_5") (pintype "passive"))
    )
    (net (code "42") (name "Net-(U1-RXD)") (class "Default")
      (node (ref "R13") (pin "1") (pinfunction "1_1") (pintype "passive"))
      (node (ref "U1") (pin "25") (pinfunction "RXD_25") (pintype "passive"))
    )
    (net (code "43") (name "Net-(U1-TXD)") (class "Default")
      (node (ref "R9") (pin "1") (pinfunction "1_1") (pintype "passive"))
      (node (ref "U1") (pin "26") (pinfunction "TXD_26") (pintype "passive"))
    )
    (net (code "44") (name "Net-(U1-VDD)") (class "Default")
      (node (ref "C3") (pin "2") (pinfunction "2_2") (pintype "passive"))
      (node (ref "C4") (pin "2") (pinfunction "2_2") (pintype "passive"))
      (node (ref "R3") (pin "2") (pinfunction "2_2") (pintype "passive"))
      (node (ref "U1") (pin "6") (pinfunction "VDD_6") (pintype "passive"))
    )
    (net (code "45") (name "Net-(U1-~{RST})") (class "Default")
      (node (ref "R3") (pin "1") (pinfunction "1_1") (pintype "passive"))
      (node (ref "U1") (pin "9") (pinfunction "~{RST}_9") (pintype "passive"))
    )
    (net (code "46") (name "Net-(U1-~{SUSPEND})") (class "Default")
      (node (ref "R6") (pin "1") (pinfunction "1_1") (pintype "passive"))
      (node (ref "U1") (pin "11") (pinfunction "~{SUSPEND}_11") (pintype "passive"))
    )
    (net (code "47") (name "Net-(U3-CPN)") (class "Default")
      (node (ref "C6") (pin "2") (pinfunction "2_2") (pintype "passive"))
      (node (ref "U3") (pin "6") (pinfunction "CPN_6") (pintype "passive"))
    )
    (net (code "48") (name "Net-(U3-CPP)") (class "Default")
      (node (ref "C6") (pin "1") (pinfunction "1_1") (pintype "passive"))
      (node (ref "U3") (pin "5") (pinfunction "CPP_5") (pintype "passive"))
    )
    (net (code "49") (name "Net-(U3-CS)") (class "Default")
      (node (ref "R10") (pin "1") (pinfunction "1_1") (pintype "passive"))
      (node (ref "U3") (pin "14") (pinfunction "CS_14") (pintype "passive"))
    )
    (net (code "50") (name "Net-(U3-RD)") (class "Default")
      (node (ref "R8") (pin "1") (pinfunction "1_1") (pintype "passive"))
      (node (ref "U3") (pin "3") (pinfunction "RD_3") (pintype "passive"))
    )
    (net (code "51") (name "Net-(U3-V5)") (class "Default")
      (node (ref "C7") (pin "2") (pinfunction "2_2") (pintype "passive"))
      (node (ref "U3") (pin "12") (pinfunction "V5_12") (pintype "passive"))
    )
    (net (code "52") (name "Net-(U3-VCP)") (class "Default")
      (node (ref "C5") (pin "1") (pinfunction "1_1") (pintype "passive"))
      (node (ref "U3") (pin "4") (pinfunction "VCP_4") (pintype "passive"))
    )
    (net (code "53") (name "Net-(U5-BYP{slash}ADJ)") (class "Default")
      (node (ref "C14") (pin "2") (pinfunction "2_2") (pintype "passive"))
      (node (ref "U5") (pin "4") (pinfunction "BYP/ADJ_4") (pintype "passive"))
    )
    (net (code "54") (name "Net-(U5-EN)") (class "Default")
      (node (ref "C10") (pin "1") (pinfunction "1_1") (pintype "passive"))
      (node (ref "C11") (pin "2") (pinfunction "2_2") (pintype "passive"))
      (node (ref "L1") (pin "2") (pinfunction "2_2") (pintype "passive"))
      (node (ref "U5") (pin "1") (pinfunction "VIN_1") (pintype "passive"))
      (node (ref "U5") (pin "3") (pinfunction "EN_3") (pintype "passive"))
    )
    (net (code "55") (name "Net-(U6--INB)") (class "Default")
      (node (ref "R23") (pin "2") (pinfunction "2_2") (pintype "passive"))
      (node (ref "R24") (pin "1") (pinfunction "1_1") (pintype "passive"))
      (node (ref "U6") (pin "6") (pinfunction "-INB_6") (pintype "passive"))
    )
    (net (code "56") (name "Net-(U8-C1N)") (class "Default")
      (node (ref "C29") (pin "1") (pinfunction "1_1") (pintype "passive"))
      (node (ref "U8") (pin "4") (pinfunction "C1N_4") (pintype "passive"))
    )
    (net (code "57") (name "Net-(U8-C1P)") (class "Default")
      (node (ref "C29") (pin "2") (pinfunction "2_2") (pintype "passive"))
      (node (ref "U8") (pin "3") (pinfunction "C1P_3") (pintype "passive"))
    )
    (net (code "58") (name "Net-(U8-C2N)") (class "Default")
      (node (ref "C28") (pin "2") (pinfunction "2_2") (pintype "passive"))
      (node (ref "U8") (pin "2") (pinfunction "C2N_2") (pintype "passive"))
    )
    (net (code "59") (name "Net-(U8-C2P)") (class "Default")
      (node (ref "C28") (pin "1") (pinfunction "1_1") (pintype "passive"))
      (node (ref "U8") (pin "1") (pinfunction "C2P_1") (pintype "passive"))
    )
    (net (code "60") (name "Net-(U8-IREF)") (class "Default")
      (node (ref "R32") (pin "1") (pinfunction "1_1") (pintype "passive"))
      (node (ref "U8") (pin "12") (pinfunction "IREF_12") (pintype "passive"))
    )
    (net (code "61") (name "Net-(U8-VCC)") (class "Default")
      (node (ref "C26") (pin "1") (pinfunction "1_1") (pintype "passive"))
      (node (ref "C27") (pin "1") (pinfunction "1_1") (pintype "passive"))
      (node (ref "U8") (pin "14") (pinfunction "VCC_14") (pintype "passive"))
    )
    (net (code "62") (name "Net-(U8-VCOMH)") (class "Default")
      (node (ref "C25") (pin "2") (pinfunction "2_2") (pintype "passive"))
      (node (ref "U8") (pin "13") (pinfunction "VCOMH_13") (pintype "passive"))
    )
    (net (code "63") (name "Net-(X1-OSC1)") (class "Default")
      (node (ref "C17") (pin "2") (pinfunction "2_2") (pintype "passive"))
      (node (ref "R26") (pin "2") (pinfunction "2_2") (pintype "passive"))
      (node (ref "X1") (pin "1") (pinfunction "OSC1_1") (pintype "passive"))
    )
    (net (code "64") (name "OLED_VDD") (class "Default")
      (node (ref "C31") (pin "2") (pinfunction "2_2") (pintype "passive"))
      (node (ref "C32") (pin "2") (pinfunction "2_2") (pintype "passive"))
      (node (ref "R28") (pin "2") (pinfunction "2_2") (pintype "passive"))
      (node (ref "R29") (pin "2") (pinfunction "2_2") (pintype "passive"))
      (node (ref "S1") (pin "7") (pinfunction "7_7") (pintype "passive"))
      (node (ref "U8") (pin "5") (pinfunction "VBAT_5") (pintype "passive"))
      (node (ref "U8") (pin "8") (pinfunction "VDD_8") (pintype "passive"))
    )
    (net (code "65") (name "VCC") (class "Default")
      (node (ref "R30") (pin "1") (pinfunction "1_1") (pintype "passive"))
    )
    (net (code "66") (name "V_M") (class "Default")
      (node (ref "C5") (pin "2") (pinfunction "2_2") (pintype "passive"))
      (node (ref "C8") (pin "1") (pinfunction "1_1") (pintype "passive"))
      (node (ref "C9") (pin "2") (pinfunction "2_2") (pintype "passive"))
      (node (ref "R16") (pin "1") (pinfunction "1_1") (pintype "passive"))
      (node (ref "T2") (pin "1") (pinfunction "1_1") (pintype "passive"))
      (node (ref "U3") (pin "11") (pinfunction "VCC_11") (pintype "passive"))
    )
    (net (code "67") (name "unconnected-(U1-CTS-Pad23)") (class "Default")
      (node (ref "U1") (pin "23") (pinfunction "CTS_23") (pintype "passive"))
    )
    (net (code "68") (name "unconnected-(U1-DCD-Pad1)") (class "Default")
      (node (ref "U1") (pin "1") (pinfunction "DCD_1") (pintype "passive"))
    )
    (net (code "69") (name "unconnected-(U1-DSR-Pad27)") (class "Default")
      (node (ref "U1") (pin "27") (pinfunction "DSR_27") (pintype "passive"))
    )
    (net (code "70") (name "unconnected-(U1-DTR-Pad28)") (class "Default")
      (node (ref "U1") (pin "28") (pinfunction "DTR_28") (pintype "passive"))
    )
    (net (code "71") (name "unconnected-(U1-NC-Pad10)") (class "Default")
      (node (ref "U1") (pin "10") (pinfunction "NC_10") (pintype "passive"))
    )
    (net (code "72") (name "unconnected-(U1-NC-Pad13)") (class "Default")
      (node (ref "U1") (pin "13") (pinfunction "NC_13") (pintype "passive"))
    )
    (net (code "73") (name "unconnected-(U1-NC-Pad14)") (class "Default")
      (node (ref "U1") (pin "14") (pinfunction "NC_14") (pintype "passive"))
    )
    (net (code "74") (name "unconnected-(U1-NC-Pad15)") (class "Default")
      (node (ref "U1") (pin "15") (pinfunction "NC_15") (pintype "passive"))
    )
    (net (code "75") (name "unconnected-(U1-NC-Pad16)") (class "Default")
      (node (ref "U1") (pin "16") (pinfunction "NC_16") (pintype "passive"))
    )
    (net (code "76") (name "unconnected-(U1-NC-Pad17)") (class "Default")
      (node (ref "U1") (pin "17") (pinfunction "NC_17") (pintype "passive"))
    )
    (net (code "77") (name "unconnected-(U1-NC-Pad18)") (class "Default")
      (node (ref "U1") (pin "18") (pinfunction "NC_18") (pintype "passive"))
    )
    (net (code "78") (name "unconnected-(U1-NC-Pad19)") (class "Default")
      (node (ref "U1") (pin "19") (pinfunction "NC_19") (pintype "passive"))
    )
    (net (code "79") (name "unconnected-(U1-NC-Pad20)") (class "Default")
      (node (ref "U1") (pin "20") (pinfunction "NC_20") (pintype "passive"))
    )
    (net (code "80") (name "unconnected-(U1-NC-Pad21)") (class "Default")
      (node (ref "U1") (pin "21") (pinfunction "NC_21") (pintype "passive"))
    )
    (net (code "81") (name "unconnected-(U1-NC-Pad22)") (class "Default")
      (node (ref "U1") (pin "22") (pinfunction "NC_22") (pintype "passive"))
    )
    (net (code "82") (name "unconnected-(U1-RI-Pad2)") (class "Default")
      (node (ref "U1") (pin "2") (pinfunction "RI_2") (pintype "passive"))
    )
    (net (code "83") (name "unconnected-(U1-RTS-Pad24)") (class "Default")
      (node (ref "U1") (pin "24") (pinfunction "RTS_24") (pintype "passive"))
    )
    (net (code "84") (name "unconnected-(U1-SUSPEND-Pad12)") (class "Default")
      (node (ref "U1") (pin "12") (pinfunction "SUSPEND_12") (pintype "passive"))
    )
    (net (code "85") (name "unconnected-(U2-D2-Pad3)") (class "Default")
      (node (ref "U2") (pin "3") (pinfunction "D2_3") (pintype "passive"))
    )
    (net (code "86") (name "unconnected-(U2-D3-Pad4)") (class "Default")
      (node (ref "U2") (pin "4") (pinfunction "D3_4") (pintype "passive"))
    )
    (net (code "87") (name "unconnected-(U4-ID-Pad4)") (class "Default")
      (node (ref "U4") (pin "4") (pinfunction "ID_4") (pintype "passive"))
    )
    (net (code "88") (name "unconnected-(U6-+INA-Pad3)") (class "Default")
      (node (ref "U6") (pin "3") (pinfunction "+INA_3") (pintype "passive"))
    )
    (net (code "89") (name "unconnected-(U6--INA-Pad2)") (class "Default")
      (node (ref "U6") (pin "2") (pinfunction "-INA_2") (pintype "passive"))
    )
    (net (code "90") (name "unconnected-(U6-OUTA-Pad1)") (class "Default")
      (node (ref "U6") (pin "1") (pinfunction "OUTA_1") (pintype "passive"))
    )
    (net (code "91") (name "unconnected-(U8-VBREF-Pad6)") (class "Default")
      (node (ref "U8") (pin "6") (pinfunction "VBREF_6") (pintype "passive"))
    )
  )
)
